# FreqStd.net
KiCad netlist of a schematic drawn in EAGLE
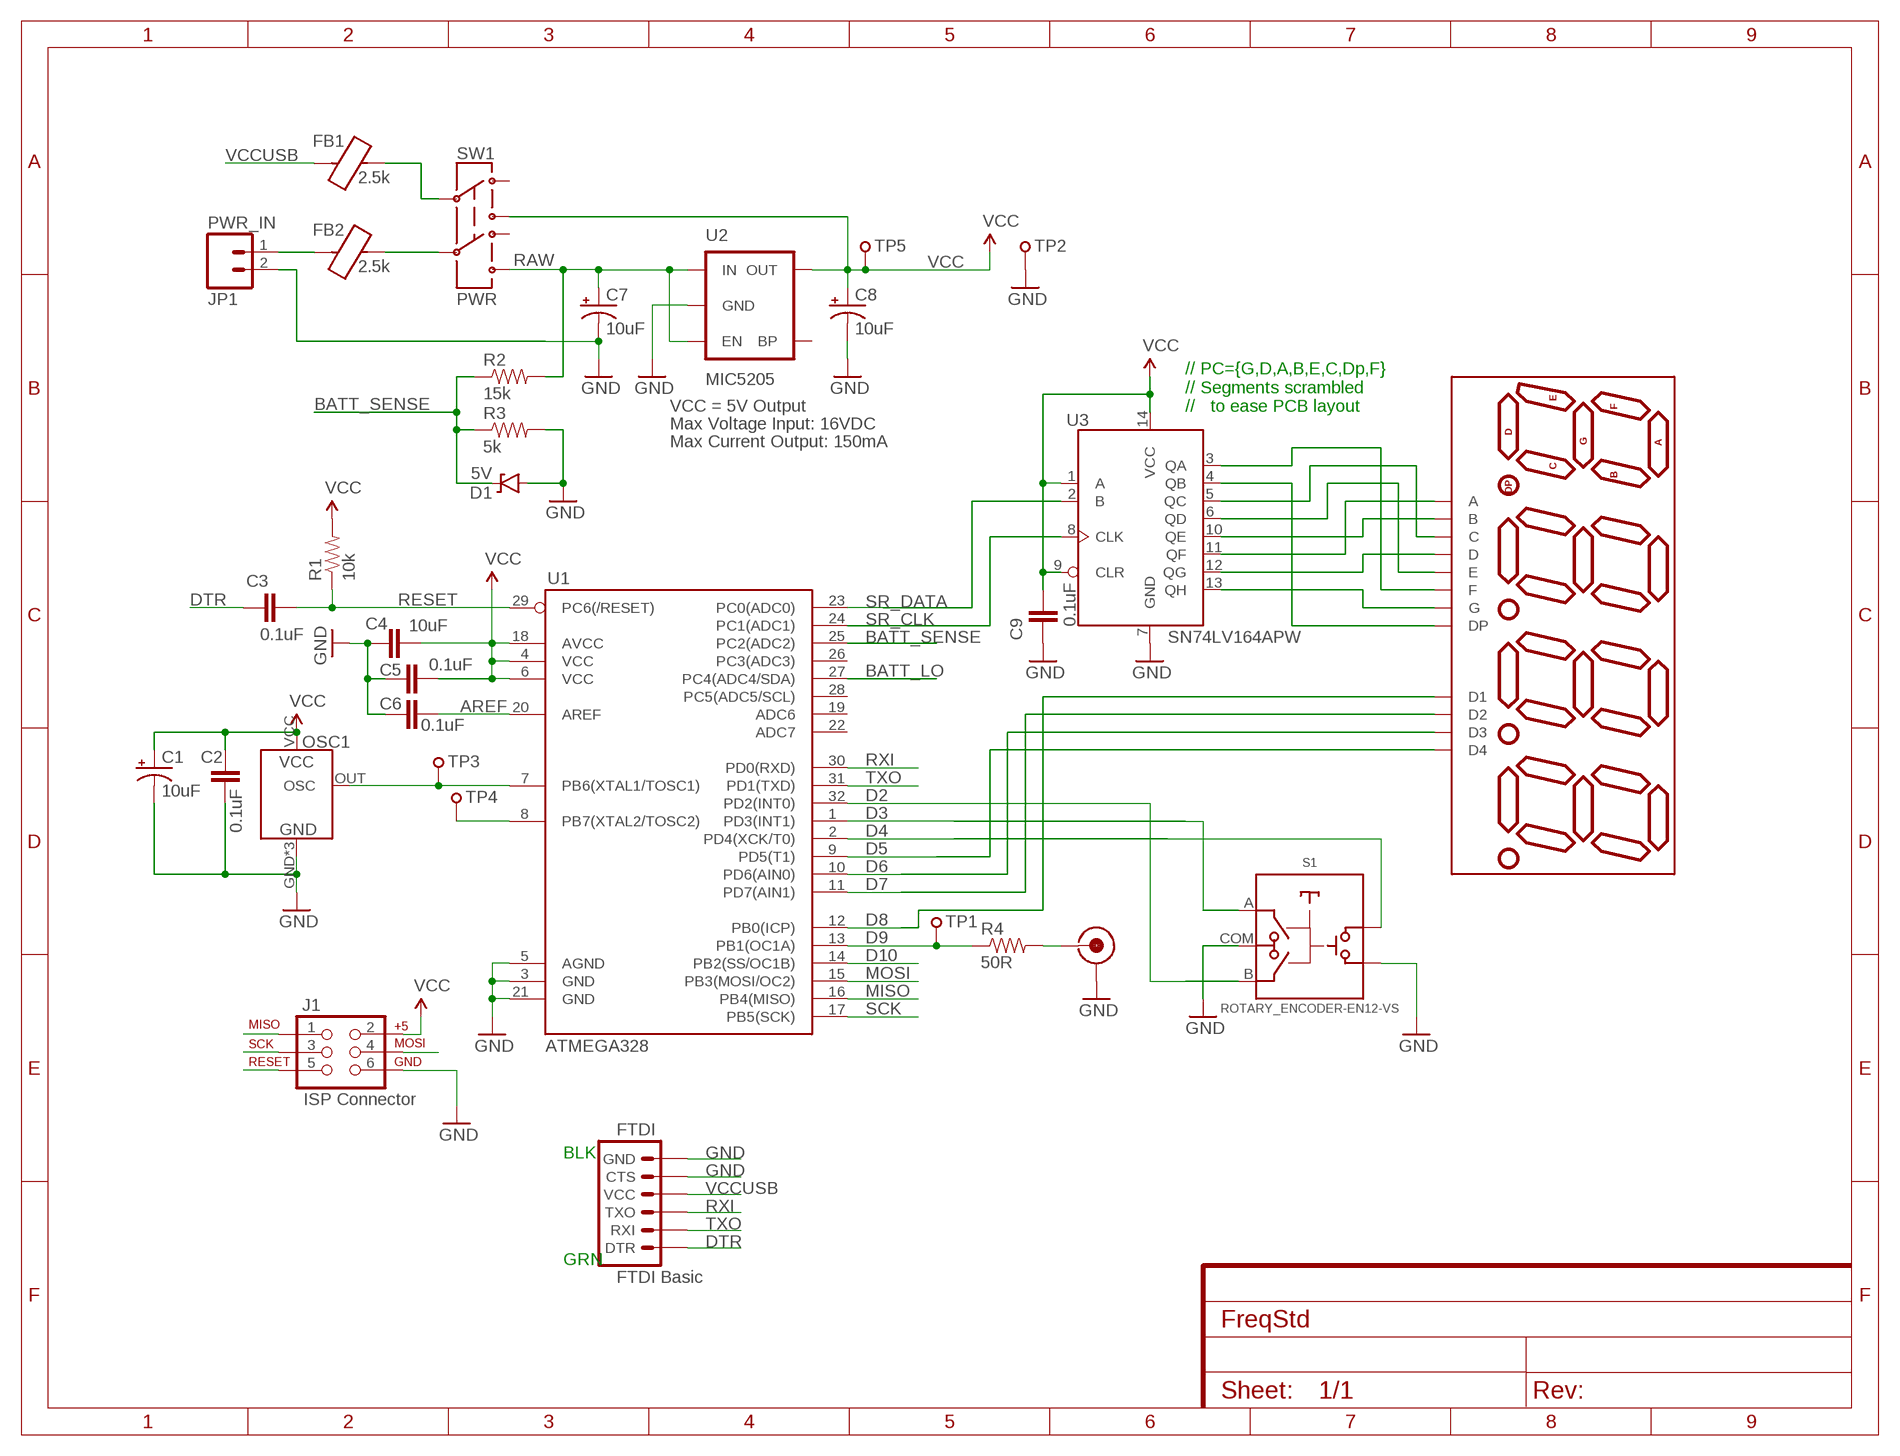
[diagram p0: schematic, sheet 1]

(export (version "E")
  (design (tool "Eeschema 10.0.6"))
  (components
    (comp (ref "C1")
      (value "10uF")
      (footprint "eagle-import:0805-POL")
      (libsource (lib "eagle-import") (part "CAP_POL0805"))
    )
    (comp (ref "C2")
      (value "0.1uF")
      (footprint "eagle-import:0805")
      (libsource (lib "eagle-import") (part "CAP0805"))
    )
    (comp (ref "C3")
      (value "0.1uF")
      (footprint "eagle-import:0805")
      (libsource (lib "eagle-import") (part "CAP0805"))
    )
    (comp (ref "C4")
      (value "10uF")
      (footprint "eagle-import:0805")
      (libsource (lib "eagle-import") (part "CAP0805"))
    )
    (comp (ref "C5")
      (value "0.1uF")
      (footprint "eagle-import:0805")
      (libsource (lib "eagle-import") (part "CAP0805"))
    )
    (comp (ref "C6")
      (value "0.1uF")
      (footprint "eagle-import:0805")
      (libsource (lib "eagle-import") (part "CAP0805"))
    )
    (comp (ref "C7")
      (value "10uF")
      (footprint "eagle-import:0805-POL")
      (libsource (lib "eagle-import") (part "CAP_POL0805"))
    )
    (comp (ref "C8")
      (value "10uF")
      (footprint "eagle-import:0805-POL")
      (libsource (lib "eagle-import") (part "CAP_POL0805"))
    )
    (comp (ref "C9")
      (value "0.1uF")
      (footprint "eagle-import:0805")
      (libsource (lib "eagle-import") (part "CAP0805"))
    )
    (comp (ref "D1")
      (value "5V")
      (footprint "eagle-import:SOD-323")
      (libsource (lib "eagle-import") (part "DIODE-ZENER3.3V"))
    )
    (comp (ref "DISP1")
      (value "HP_DISPLAY")
      (footprint "eagle-import:DIL12")
      (libsource (lib "eagle-import") (part "HP_DISPLAY"))
    )
    (comp (ref "FB1")
      (value "2.5k")
      (footprint "eagle-import:0805")
      (libsource (lib "eagle-import") (part "FERRITE_BEAD_0805"))
    )
    (comp (ref "FB2")
      (value "2.5k")
      (footprint "eagle-import:0805")
      (libsource (lib "eagle-import") (part "FERRITE_BEAD_0805"))
    )
    (comp (ref "FRAME1")
      (value "FRAME_LTR_CU_MARK")
      (footprint "eagle-import:FR-LTR-ON-PCB")
      (fields
        (field (name "CNAME") "Frequency Standard")
        (field (name "CREVISION") "Rev A")
        (field (name "DESIGNER") "C.Schnarel")
      )
      (libsource (lib "eagle-import") (part "FRAME_LTR_CU_MARK"))
    )
    (comp (ref "FTDI")
      (value "FTDI Basic")
      (footprint "eagle-import:1X06")
      (libsource (lib "eagle-import") (part "ARDUINO_SERIAL_PROGRAMPTH"))
    )
    (comp (ref "J1")
      (value "ISP Connector")
      (footprint "eagle-import:2X3")
      (libsource (lib "eagle-import") (part "AVR_SPI_PRG_6PTH"))
    )
    (comp (ref "J2")
      (value "BNC_RIGHT-ANGLE")
      (footprint "eagle-import:BNC-RIGHT-ANGLE")
      (libsource (lib "eagle-import") (part "BNC_RIGHT-ANGLE"))
    )
    (comp (ref "JP1")
      (value "PWR_IN")
      (footprint "eagle-import:MOLEX-1X2")
      (libsource (lib "eagle-import") (part "M02POLAR"))
    )
    (comp (ref "OSC1")
      (value "TCXO-RTXO230LC")
      (footprint "eagle-import:TCXO")
      (libsource (lib "eagle-import") (part "TCXO-RTXO230LC"))
    )
    (comp (ref "R1")
      (value "10k")
      (footprint "eagle-import:0805")
      (libsource (lib "eagle-import") (part "RESISTOR0805-RES"))
    )
    (comp (ref "R2")
      (value "15k")
      (footprint "eagle-import:0805")
      (libsource (lib "eagle-import") (part "RESISTOR0805-RES"))
    )
    (comp (ref "R3")
      (value "5k")
      (footprint "eagle-import:0805")
      (libsource (lib "eagle-import") (part "RESISTOR0805-RES"))
    )
    (comp (ref "R4")
      (value "50R")
      (footprint "eagle-import:0805")
      (libsource (lib "eagle-import") (part "RESISTOR0805-RES"))
    )
    (comp (ref "S1")
      (value "ROTARY_ENCODER-EN12-VS")
      (footprint "eagle-import:EN12-VS")
      (libsource (lib "eagle-import") (part "ROTARY_ENCODER-EN12-VS"))
    )
    (comp (ref "SW1")
      (value "PWR")
      (footprint "eagle-import:8X10_BUTTON_ROUND")
      (libsource (lib "eagle-import") (part "SWITCH,BUTTON,ROUND,7MM"))
    )
    (comp (ref "TP1")
      (value "TEST_POINT")
      (footprint "eagle-import:BBD-VIA")
      (libsource (lib "eagle-import") (part "TEST_POINT"))
    )
    (comp (ref "TP2")
      (value "TEST_POINT")
      (footprint "eagle-import:BBD-VIA")
      (libsource (lib "eagle-import") (part "TEST_POINT"))
    )
    (comp (ref "TP3")
      (value "TEST_POINT")
      (footprint "eagle-import:BBD-VIA")
      (libsource (lib "eagle-import") (part "TEST_POINT"))
    )
    (comp (ref "TP4")
      (value "TEST_POINT")
      (footprint "eagle-import:BBD-VIA")
      (libsource (lib "eagle-import") (part "TEST_POINT"))
    )
    (comp (ref "TP5")
      (value "TEST_POINT")
      (footprint "eagle-import:BBD-VIA")
      (libsource (lib "eagle-import") (part "TEST_POINT"))
    )
    (comp (ref "U1")
      (value "ATMEGA328")
      (footprint "eagle-import:TQFP32-08")
      (libsource (lib "eagle-import") (part "ATMEGA168"))
    )
    (comp (ref "U2")
      (value "MIC5205")
      (footprint "eagle-import:SOT23-5")
      (libsource (lib "eagle-import") (part "V_REG_LDOSMD"))
    )
    (comp (ref "U3")
      (value "SN74LV164APW")
      (footprint "eagle-import:TSSOP-14(TI)")
      (libsource (lib "eagle-import") (part "SN74LV164APW"))
    )
  )
  (nets
    (net (code "1") (name "/AREF") (class "Default")
      (node (ref "C6") (pin "2") (pinfunction "2_2") (pintype "passive"))
      (node (ref "U1") (pin "20") (pinfunction "AREF_20") (pintype "bidirectional"))
    )
    (net (code "2") (name "/BATT_LO") (class "Default")
      (node (ref "U1") (pin "27") (pinfunction "PC4(ADC4/SDA)_27") (pintype "bidirectional"))
    )
    (net (code "3") (name "/BATT_SENSE") (class "Default")
      (node (ref "D1") (pin "C") (pinfunction "C_C") (pintype "passive"))
      (node (ref "R2") (pin "1") (pinfunction "1_1") (pintype "passive"))
      (node (ref "R3") (pin "1") (pinfunction "1_1") (pintype "passive"))
      (node (ref "U1") (pin "25") (pinfunction "PC2(ADC2)_25") (pintype "bidirectional"))
    )
    (net (code "4") (name "/D2") (class "Default")
      (node (ref "S1") (pin "B") (pinfunction "B_B") (pintype "bidirectional"))
      (node (ref "U1") (pin "32") (pinfunction "PD2(INT0)_32") (pintype "bidirectional"))
    )
    (net (code "5") (name "/D3") (class "Default")
      (node (ref "S1") (pin "A") (pinfunction "A_A") (pintype "bidirectional"))
      (node (ref "U1") (pin "1") (pinfunction "PD3(INT1)_1") (pintype "bidirectional"))
    )
    (net (code "6") (name "/D4") (class "Default")
      (node (ref "S1") (pin "D") (pinfunction "P$4_D") (pintype "bidirectional"))
      (node (ref "U1") (pin "2") (pinfunction "PD4(XCK/T0)_2") (pintype "bidirectional"))
    )
    (net (code "7") (name "/D5") (class "Default")
      (node (ref "DISP1") (pin "6") (pinfunction "D4_6") (pintype "bidirectional"))
      (node (ref "U1") (pin "9") (pinfunction "PD5(T1)_9") (pintype "bidirectional"))
    )
    (net (code "8") (name "/D6") (class "Default")
      (node (ref "DISP1") (pin "4") (pinfunction "D3_4") (pintype "bidirectional"))
      (node (ref "U1") (pin "10") (pinfunction "PD6(AIN0)_10") (pintype "bidirectional"))
    )
    (net (code "9") (name "/D7") (class "Default")
      (node (ref "DISP1") (pin "10") (pinfunction "D2_10") (pintype "bidirectional"))
      (node (ref "U1") (pin "11") (pinfunction "PD7(AIN1)_11") (pintype "bidirectional"))
    )
    (net (code "10") (name "/D8") (class "Default")
      (node (ref "DISP1") (pin "1") (pinfunction "D1_1") (pintype "bidirectional"))
      (node (ref "U1") (pin "12") (pinfunction "PB0(ICP)_12") (pintype "bidirectional"))
    )
    (net (code "11") (name "/D9") (class "Default")
      (node (ref "R4") (pin "1") (pinfunction "1_1") (pintype "passive"))
      (node (ref "TP1") (pin "P$1") (pinfunction "P$1_P$1") (pintype "bidirectional"))
      (node (ref "U1") (pin "13") (pinfunction "PB1(OC1A)_13") (pintype "bidirectional"))
    )
    (net (code "12") (name "/D10") (class "Default")
      (node (ref "U1") (pin "14") (pinfunction "PB2(SS/OC1B)_14") (pintype "bidirectional"))
    )
    (net (code "13") (name "/DTR") (class "Default")
      (node (ref "C3") (pin "1") (pinfunction "1_1") (pintype "passive"))
      (node (ref "FTDI") (pin "1") (pinfunction "DTR_1") (pintype "passive"))
    )
    (net (code "14") (name "/MISO") (class "Default")
      (node (ref "J1") (pin "1") (pinfunction "1_1") (pintype "passive"))
      (node (ref "U1") (pin "16") (pinfunction "PB4(MISO)_16") (pintype "bidirectional"))
    )
    (net (code "15") (name "/MOSI") (class "Default")
      (node (ref "J1") (pin "4") (pinfunction "4_4") (pintype "passive"))
      (node (ref "U1") (pin "15") (pinfunction "PB3(MOSI/OC2)_15") (pintype "bidirectional"))
    )
    (net (code "16") (name "/RAW") (class "Default")
      (node (ref "C7") (pin "1") (pinfunction "+_1") (pintype "passive"))
      (node (ref "R2") (pin "2") (pinfunction "2_2") (pintype "passive"))
      (node (ref "SW1") (pin "2NO") (pinfunction "2NO_2NO") (pintype "bidirectional"))
      (node (ref "U2") (pin "1") (pinfunction "IN_1") (pintype "input"))
      (node (ref "U2") (pin "3") (pinfunction "EN_3") (pintype "input"))
    )
    (net (code "17") (name "/RESET") (class "Default")
      (node (ref "C3") (pin "2") (pinfunction "2_2") (pintype "passive"))
      (node (ref "J1") (pin "5") (pinfunction "5_5") (pintype "passive"))
      (node (ref "R1") (pin "1") (pinfunction "1_1") (pintype "passive"))
      (node (ref "U1") (pin "29") (pinfunction "PC6(/RESET)_29") (pintype "bidirectional"))
    )
    (net (code "18") (name "/RXI") (class "Default")
      (node (ref "FTDI") (pin "3") (pinfunction "TXO_3") (pintype "passive"))
      (node (ref "U1") (pin "30") (pinfunction "PD0(RXD)_30") (pintype "bidirectional"))
    )
    (net (code "19") (name "/SCK") (class "Default")
      (node (ref "J1") (pin "3") (pinfunction "3_3") (pintype "passive"))
      (node (ref "U1") (pin "17") (pinfunction "PB5(SCK)_17") (pintype "bidirectional"))
    )
    (net (code "20") (name "/SR_CLK") (class "Default")
      (node (ref "U1") (pin "24") (pinfunction "PC1(ADC1)_24") (pintype "bidirectional"))
      (node (ref "U3") (pin "8") (pinfunction "CLK_8") (pintype "input"))
    )
    (net (code "21") (name "/SR_DATA") (class "Default")
      (node (ref "U1") (pin "23") (pinfunction "PC0(ADC0)_23") (pintype "bidirectional"))
      (node (ref "U3") (pin "2") (pinfunction "B_2") (pintype "input"))
    )
    (net (code "22") (name "/TXO") (class "Default")
      (node (ref "FTDI") (pin "2") (pinfunction "RXI_2") (pintype "passive"))
      (node (ref "U1") (pin "31") (pinfunction "PD1(TXD)_31") (pintype "bidirectional"))
    )
    (net (code "23") (name "/VCCUSB") (class "Default")
      (node (ref "FB1") (pin "1") (pinfunction "1_1") (pintype "passive"))
      (node (ref "FTDI") (pin "4") (pinfunction "VCC_4") (pintype "passive"))
    )
    (net (code "24") (name "GND") (class "Default")
      (node (ref "C1") (pin "2") (pinfunction "-_2") (pintype "passive"))
      (node (ref "C2") (pin "1") (pinfunction "1_1") (pintype "passive"))
      (node (ref "C4") (pin "1") (pinfunction "1_1") (pintype "passive"))
      (node (ref "C5") (pin "1") (pinfunction "1_1") (pintype "passive"))
      (node (ref "C6") (pin "1") (pinfunction "1_1") (pintype "passive"))
      (node (ref "C7") (pin "2") (pinfunction "-_2") (pintype "passive"))
      (node (ref "C8") (pin "2") (pinfunction "-_2") (pintype "passive"))
      (node (ref "C9") (pin "1") (pinfunction "1_1") (pintype "passive"))
      (node (ref "D1") (pin "A") (pinfunction "A_A") (pintype "passive"))
      (node (ref "FTDI") (pin "5") (pinfunction "CTS_5") (pintype "passive"))
      (node (ref "FTDI") (pin "6") (pinfunction "GND_6") (pintype "passive"))
      (node (ref "J1") (pin "6") (pinfunction "6_6") (pintype "passive"))
      (node (ref "J2") (pin "SHD") (pinfunction "SHD_SHD") (pintype "bidirectional"))
      (node (ref "JP1") (pin "2") (pinfunction "2_2") (pintype "passive"))
      (node (ref "OSC1") (pin "GND") (pinfunction "GND_GND") (pintype "bidirectional"))
      (node (ref "OSC1") (pin "SHLD1") (pinfunction "GND_SHLD1") (pintype "bidirectional"))
      (node (ref "OSC1") (pin "SHLD2") (pinfunction "GND_SHLD2") (pintype "bidirectional"))
      (node (ref "R3") (pin "2") (pinfunction "2_2") (pintype "passive"))
      (node (ref "S1") (pin "COM") (pinfunction "COM_COM") (pintype "bidirectional"))
      (node (ref "S1") (pin "E") (pinfunction "P$5_E") (pintype "bidirectional"))
      (node (ref "TP2") (pin "P$1") (pinfunction "P$1_P$1") (pintype "bidirectional"))
      (node (ref "U1") (pin "21") (pinfunction "GND_21") (pintype "bidirectional"))
      (node (ref "U1") (pin "3") (pinfunction "GND_3") (pintype "bidirectional"))
      (node (ref "U1") (pin "5") (pinfunction "AGND_5") (pintype "bidirectional"))
      (node (ref "U2") (pin "2") (pinfunction "GND_2") (pintype "input"))
      (node (ref "U3") (pin "7") (pinfunction "GND_7") (pintype "power_in"))
    )
    (net (code "25") (name "Net-(DISP1-A)") (class "Default")
      (node (ref "DISP1") (pin "12") (pinfunction "A_12") (pintype "bidirectional"))
      (node (ref "U3") (pin "11") (pinfunction "QF_11") (pintype "bidirectional"))
    )
    (net (code "26") (name "Net-(DISP1-B)") (class "Default")
      (node (ref "DISP1") (pin "11") (pinfunction "B_11") (pintype "bidirectional"))
      (node (ref "U3") (pin "10") (pinfunction "QE_10") (pintype "bidirectional"))
    )
    (net (code "27") (name "Net-(DISP1-C)") (class "Default")
      (node (ref "DISP1") (pin "3") (pinfunction "C_3") (pintype "bidirectional"))
      (node (ref "U3") (pin "5") (pinfunction "QC_5") (pintype "bidirectional"))
    )
    (net (code "28") (name "Net-(DISP1-D)") (class "Default")
      (node (ref "DISP1") (pin "8") (pinfunction "D_8") (pintype "bidirectional"))
      (node (ref "U3") (pin "12") (pinfunction "QG_12") (pintype "bidirectional"))
    )
    (net (code "29") (name "Net-(DISP1-DP)") (class "Default")
      (node (ref "DISP1") (pin "5") (pinfunction "DP_5") (pintype "bidirectional"))
      (node (ref "U3") (pin "4") (pinfunction "QB_4") (pintype "bidirectional"))
    )
    (net (code "30") (name "Net-(DISP1-E)") (class "Default")
      (node (ref "DISP1") (pin "2") (pinfunction "E_2") (pintype "bidirectional"))
      (node (ref "U3") (pin "6") (pinfunction "QD_6") (pintype "bidirectional"))
    )
    (net (code "31") (name "Net-(DISP1-F)") (class "Default")
      (node (ref "DISP1") (pin "9") (pinfunction "F_9") (pintype "bidirectional"))
      (node (ref "U3") (pin "3") (pinfunction "QA_3") (pintype "bidirectional"))
    )
    (net (code "32") (name "Net-(DISP1-G)") (class "Default")
      (node (ref "DISP1") (pin "7") (pinfunction "G_7") (pintype "bidirectional"))
      (node (ref "U3") (pin "13") (pinfunction "QH_13") (pintype "bidirectional"))
    )
    (net (code "33") (name "Net-(FB1-Pad2)") (class "Default")
      (node (ref "FB1") (pin "2") (pinfunction "2_2") (pintype "passive"))
      (node (ref "SW1") (pin "1C") (pinfunction "1C_1C") (pintype "bidirectional"))
    )
    (net (code "34") (name "Net-(FB2-Pad1)") (class "Default")
      (node (ref "FB2") (pin "1") (pinfunction "1_1") (pintype "passive"))
      (node (ref "JP1") (pin "1") (pinfunction "1_1") (pintype "passive"))
    )
    (net (code "35") (name "Net-(FB2-Pad2)") (class "Default")
      (node (ref "FB2") (pin "2") (pinfunction "2_2") (pintype "passive"))
      (node (ref "SW1") (pin "2C") (pinfunction "2C_2C") (pintype "bidirectional"))
    )
    (net (code "36") (name "Net-(J2-PadCTR)") (class "Default")
      (node (ref "J2") (pin "CTR") (pinfunction "CTR_CTR") (pintype "bidirectional"))
      (node (ref "R4") (pin "2") (pinfunction "2_2") (pintype "passive"))
    )
    (net (code "37") (name "Net-(OSC1-OSC)") (class "Default")
      (node (ref "OSC1") (pin "OUT") (pinfunction "OSC_OUT") (pintype "bidirectional"))
      (node (ref "TP3") (pin "P$1") (pinfunction "P$1_P$1") (pintype "bidirectional"))
      (node (ref "U1") (pin "7") (pinfunction "PB6(XTAL1/TOSC1)_7") (pintype "bidirectional"))
    )
    (net (code "38") (name "Net-(U1-PB7(XTAL2{slash}TOSC2))") (class "Default")
      (node (ref "TP4") (pin "P$1") (pinfunction "P$1_P$1") (pintype "bidirectional"))
      (node (ref "U1") (pin "8") (pinfunction "PB7(XTAL2/TOSC2)_8") (pintype "bidirectional"))
    )
    (net (code "39") (name "VCC") (class "Default")
      (node (ref "C1") (pin "1") (pinfunction "+_1") (pintype "passive"))
      (node (ref "C2") (pin "2") (pinfunction "2_2") (pintype "passive"))
      (node (ref "C4") (pin "2") (pinfunction "2_2") (pintype "passive"))
      (node (ref "C5") (pin "2") (pinfunction "2_2") (pintype "passive"))
      (node (ref "C8") (pin "1") (pinfunction "+_1") (pintype "passive"))
      (node (ref "C9") (pin "2") (pinfunction "2_2") (pintype "passive"))
      (node (ref "J1") (pin "2") (pinfunction "2_2") (pintype "passive"))
      (node (ref "OSC1") (pin "VCC") (pinfunction "VCC_VCC") (pintype "bidirectional"))
      (node (ref "R1") (pin "2") (pinfunction "2_2") (pintype "passive"))
      (node (ref "SW1") (pin "1NO") (pinfunction "1NO_1NO") (pintype "bidirectional"))
      (node (ref "TP5") (pin "P$1") (pinfunction "P$1_P$1") (pintype "bidirectional"))
      (node (ref "U1") (pin "18") (pinfunction "AVCC_18") (pintype "bidirectional"))
      (node (ref "U1") (pin "4") (pinfunction "VCC_4") (pintype "bidirectional"))
      (node (ref "U1") (pin "6") (pinfunction "VCC_6") (pintype "bidirectional"))
      (node (ref "U2") (pin "5") (pinfunction "OUT_5") (pintype "passive"))
      (node (ref "U3") (pin "1") (pinfunction "A_1") (pintype "bidirectional"))
      (node (ref "U3") (pin "14") (pinfunction "VCC_14") (pintype "power_in"))
      (node (ref "U3") (pin "9") (pinfunction "CLR_9") (pintype "bidirectional"))
    )
    (net (code "40") (name "unconnected-(SW1-Pad1NC)") (class "Default")
      (node (ref "SW1") (pin "1NC") (pinfunction "1NC_1NC") (pintype "bidirectional"))
    )
    (net (code "41") (name "unconnected-(SW1-Pad2NC)") (class "Default")
      (node (ref "SW1") (pin "2NC") (pinfunction "2NC_2NC") (pintype "bidirectional"))
    )
    (net (code "42") (name "unconnected-(U1-ADC6-Pad19)") (class "Default")
      (node (ref "U1") (pin "19") (pinfunction "ADC6_19") (pintype "bidirectional"))
    )
    (net (code "43") (name "unconnected-(U1-ADC7-Pad22)") (class "Default")
      (node (ref "U1") (pin "22") (pinfunction "ADC7_22") (pintype "bidirectional"))
    )
    (net (code "44") (name "unconnected-(U1-PC3(ADC3)-Pad26)") (class "Default")
      (node (ref "U1") (pin "26") (pinfunction "PC3(ADC3)_26") (pintype "bidirectional"))
    )
    (net (code "45") (name "unconnected-(U1-PC5(ADC5{slash}SCL)-Pad28)") (class "Default")
      (node (ref "U1") (pin "28") (pinfunction "PC5(ADC5/SCL)_28") (pintype "bidirectional"))
    )
    (net (code "46") (name "unconnected-(U2-BP-Pad4)") (class "Default")
      (node (ref "U2") (pin "4") (pinfunction "BP_4") (pintype "input"))
    )
  )
)
